# potuino.net
KiCad netlist of a schematic drawn in EAGLE
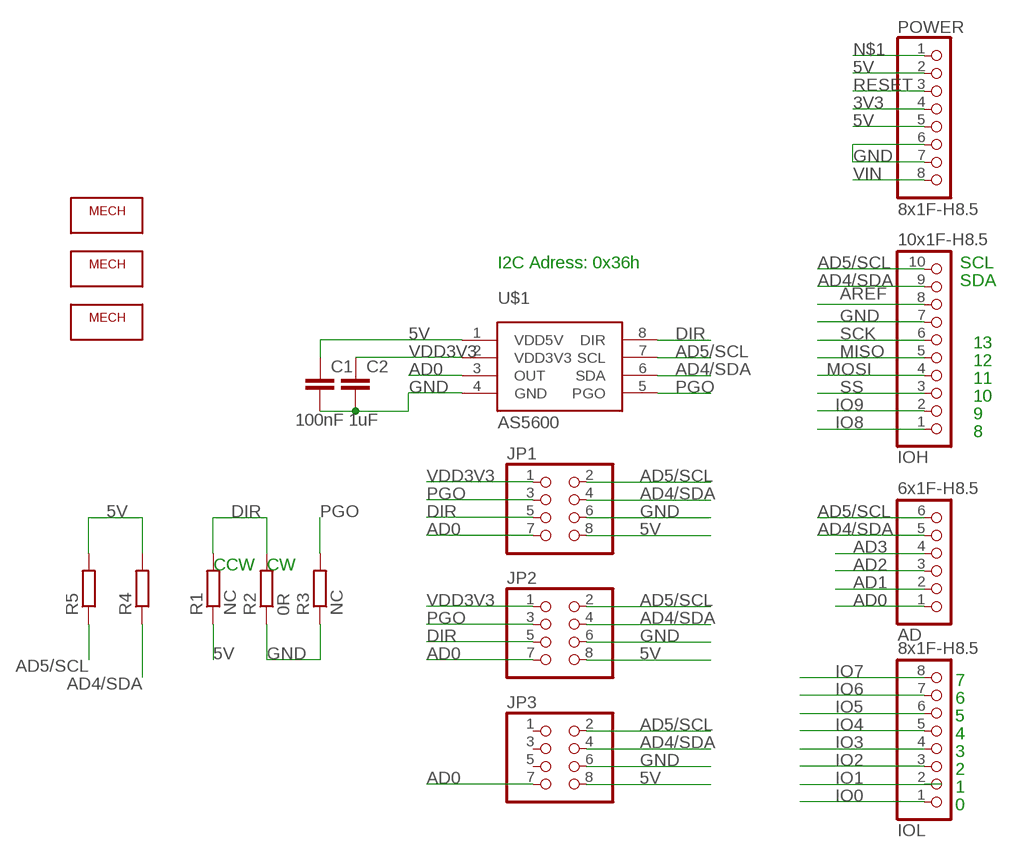
[diagram p0: schematic, sheet 1]

(export (version "E")
  (design (tool "Eeschema 10.0.6"))
  (components
    (comp (ref "AD")
      (value "6x1F-H8.5")
      (footprint "eagle-import:1X06")
      (libsource (lib "eagle-import") (part "PINHD-1X6"))
    )
    (comp (ref "C1")
      (value "100nF")
      (footprint "eagle-import:C0805")
      (libsource (lib "eagle-import") (part "C-EUC0805"))
    )
    (comp (ref "C2")
      (value "1uF")
      (footprint "eagle-import:C0805")
      (libsource (lib "eagle-import") (part "C-EUC0805"))
    )
    (comp (ref "IOH")
      (value "10x1F-H8.5")
      (footprint "eagle-import:1X10")
      (libsource (lib "eagle-import") (part "PINHD-1X10_ARD"))
    )
    (comp (ref "IOL")
      (value "8x1F-H8.5")
      (footprint "eagle-import:1X08")
      (libsource (lib "eagle-import") (part "PINHD-1X8"))
    )
    (comp (ref "JP1")
      (value "PINHD-2X04_2.54")
      (footprint "eagle-import:2X04")
      (libsource (lib "eagle-import") (part "PINHD-2X04_2.54"))
    )
    (comp (ref "JP2")
      (value "PINHD-2X04_2.54")
      (footprint "eagle-import:2X04")
      (libsource (lib "eagle-import") (part "PINHD-2X04_2.54"))
    )
    (comp (ref "JP3")
      (value "PINHD-2X04_2.54")
      (footprint "eagle-import:2X04")
      (libsource (lib "eagle-import") (part "PINHD-2X04_2.54"))
    )
    (comp (ref "POWER")
      (value "8x1F-H8.5")
      (footprint "eagle-import:1X08")
      (libsource (lib "eagle-import") (part "PINHD-1X8"))
    )
    (comp (ref "R1")
      (value "NC")
      (footprint "eagle-import:R0603")
      (libsource (lib "eagle-import") (part "R-EU_R0603"))
    )
    (comp (ref "R2")
      (value "0R")
      (footprint "eagle-import:R0603")
      (libsource (lib "eagle-import") (part "R-EU_R0603"))
    )
    (comp (ref "R3")
      (value "NC")
      (footprint "eagle-import:R0603")
      (libsource (lib "eagle-import") (part "R-EU_R0603"))
    )
    (comp (ref "R4")
      (value "R-EU_R0603")
      (footprint "eagle-import:R0603")
      (libsource (lib "eagle-import") (part "R-EU_R0603"))
    )
    (comp (ref "R5")
      (value "R-EU_R0603")
      (footprint "eagle-import:R0603")
      (libsource (lib "eagle-import") (part "R-EU_R0603"))
    )
    (comp (ref "U$1")
      (value "AS5600")
      (footprint "eagle-import:SO08")
      (libsource (lib "eagle-import") (part "AS5600"))
    )
    (comp (ref "U$2")
      (value "MECHANICAL")
      (footprint "eagle-import:MECHANICAL-PARTS")
      (libsource (lib "eagle-import") (part "MECHANICAL"))
    )
    (comp (ref "U$3")
      (value "MECHANICAL")
      (footprint "eagle-import:MECHANICAL-PARTS")
      (libsource (lib "eagle-import") (part "MECHANICAL"))
    )
    (comp (ref "U$4")
      (value "MECHANICAL2")
      (footprint "eagle-import:MECHANICAL-TOP")
      (libsource (lib "eagle-import") (part "MECHANICAL2"))
    )
  )
  (nets
    (net (code "1") (name "/3V3") (class "Default")
      (node (ref "POWER") (pin "4") (pinfunction "4_4") (pintype "passive"))
    )
    (net (code "2") (name "/5V") (class "Default")
      (node (ref "C1") (pin "1") (pinfunction "1_1") (pintype "passive"))
      (node (ref "JP1") (pin "8") (pinfunction "8_8") (pintype "passive"))
      (node (ref "JP2") (pin "8") (pinfunction "8_8") (pintype "passive"))
      (node (ref "JP3") (pin "8") (pinfunction "8_8") (pintype "passive"))
      (node (ref "POWER") (pin "2") (pinfunction "2_2") (pintype "passive"))
      (node (ref "POWER") (pin "5") (pinfunction "5_5") (pintype "passive"))
      (node (ref "R1") (pin "1") (pinfunction "1_1") (pintype "passive"))
      (node (ref "R4") (pin "2") (pinfunction "2_2") (pintype "passive"))
      (node (ref "R5") (pin "2") (pinfunction "2_2") (pintype "passive"))
      (node (ref "U$1") (pin "1") (pinfunction "VDD5V_1") (pintype "bidirectional"))
    )
    (net (code "3") (name "/AD0") (class "Default")
      (node (ref "AD") (pin "1") (pinfunction "1_1") (pintype "passive"))
      (node (ref "JP1") (pin "7") (pinfunction "7_7") (pintype "passive"))
      (node (ref "JP2") (pin "7") (pinfunction "7_7") (pintype "passive"))
      (node (ref "JP3") (pin "7") (pinfunction "7_7") (pintype "passive"))
      (node (ref "U$1") (pin "3") (pinfunction "OUT_3") (pintype "bidirectional"))
    )
    (net (code "4") (name "/AD1") (class "Default")
      (node (ref "AD") (pin "2") (pinfunction "2_2") (pintype "passive"))
    )
    (net (code "5") (name "/AD2") (class "Default")
      (node (ref "AD") (pin "3") (pinfunction "3_3") (pintype "passive"))
    )
    (net (code "6") (name "/AD3") (class "Default")
      (node (ref "AD") (pin "4") (pinfunction "4_4") (pintype "passive"))
    )
    (net (code "7") (name "/AD4{slash}SDA") (class "Default")
      (node (ref "AD") (pin "5") (pinfunction "5_5") (pintype "passive"))
      (node (ref "IOH") (pin "9") (pinfunction "9_9") (pintype "passive"))
      (node (ref "JP1") (pin "4") (pinfunction "4_4") (pintype "passive"))
      (node (ref "JP2") (pin "4") (pinfunction "4_4") (pintype "passive"))
      (node (ref "JP3") (pin "4") (pinfunction "4_4") (pintype "passive"))
      (node (ref "R4") (pin "1") (pinfunction "1_1") (pintype "passive"))
      (node (ref "U$1") (pin "6") (pinfunction "SDA_6") (pintype "bidirectional"))
    )
    (net (code "8") (name "/AD5{slash}SCL") (class "Default")
      (node (ref "AD") (pin "6") (pinfunction "6_6") (pintype "passive"))
      (node (ref "IOH") (pin "10") (pinfunction "10_10") (pintype "passive"))
      (node (ref "JP1") (pin "2") (pinfunction "2_2") (pintype "passive"))
      (node (ref "JP2") (pin "2") (pinfunction "2_2") (pintype "passive"))
      (node (ref "JP3") (pin "2") (pinfunction "2_2") (pintype "passive"))
      (node (ref "R5") (pin "1") (pinfunction "1_1") (pintype "passive"))
      (node (ref "U$1") (pin "7") (pinfunction "SCL_7") (pintype "bidirectional"))
    )
    (net (code "9") (name "/AREF") (class "Default")
      (node (ref "IOH") (pin "8") (pinfunction "8_8") (pintype "passive"))
    )
    (net (code "10") (name "/DIR") (class "Default")
      (node (ref "JP1") (pin "5") (pinfunction "5_5") (pintype "passive"))
      (node (ref "JP2") (pin "5") (pinfunction "5_5") (pintype "passive"))
      (node (ref "R1") (pin "2") (pinfunction "2_2") (pintype "passive"))
      (node (ref "R2") (pin "2") (pinfunction "2_2") (pintype "passive"))
      (node (ref "U$1") (pin "8") (pinfunction "DIR_8") (pintype "bidirectional"))
    )
    (net (code "11") (name "/GND") (class "Default")
      (node (ref "C1") (pin "2") (pinfunction "2_2") (pintype "passive"))
      (node (ref "C2") (pin "2") (pinfunction "2_2") (pintype "passive"))
      (node (ref "IOH") (pin "7") (pinfunction "7_7") (pintype "passive"))
      (node (ref "JP1") (pin "6") (pinfunction "6_6") (pintype "passive"))
      (node (ref "JP2") (pin "6") (pinfunction "6_6") (pintype "passive"))
      (node (ref "JP3") (pin "6") (pinfunction "6_6") (pintype "passive"))
      (node (ref "POWER") (pin "6") (pinfunction "6_6") (pintype "passive"))
      (node (ref "POWER") (pin "7") (pinfunction "7_7") (pintype "passive"))
      (node (ref "R2") (pin "1") (pinfunction "1_1") (pintype "passive"))
      (node (ref "R3") (pin "1") (pinfunction "1_1") (pintype "passive"))
      (node (ref "U$1") (pin "4") (pinfunction "GND_4") (pintype "bidirectional"))
    )
    (net (code "12") (name "/IO0") (class "Default")
      (node (ref "IOL") (pin "1") (pinfunction "1_1") (pintype "passive"))
    )
    (net (code "13") (name "/IO1") (class "Default")
      (node (ref "IOL") (pin "2") (pinfunction "2_2") (pintype "passive"))
    )
    (net (code "14") (name "/IO2") (class "Default")
      (node (ref "IOL") (pin "3") (pinfunction "3_3") (pintype "passive"))
    )
    (net (code "15") (name "/IO3") (class "Default")
      (node (ref "IOL") (pin "4") (pinfunction "4_4") (pintype "passive"))
    )
    (net (code "16") (name "/IO4") (class "Default")
      (node (ref "IOL") (pin "5") (pinfunction "5_5") (pintype "passive"))
    )
    (net (code "17") (name "/IO5") (class "Default")
      (node (ref "IOL") (pin "6") (pinfunction "6_6") (pintype "passive"))
    )
    (net (code "18") (name "/IO6") (class "Default")
      (node (ref "IOL") (pin "7") (pinfunction "7_7") (pintype "passive"))
    )
    (net (code "19") (name "/IO7") (class "Default")
      (node (ref "IOL") (pin "8") (pinfunction "8_8") (pintype "passive"))
    )
    (net (code "20") (name "/IO8") (class "Default")
      (node (ref "IOH") (pin "1") (pinfunction "1_1") (pintype "passive"))
    )
    (net (code "21") (name "/IO9") (class "Default")
      (node (ref "IOH") (pin "2") (pinfunction "2_2") (pintype "passive"))
    )
    (net (code "22") (name "/MISO") (class "Default")
      (node (ref "IOH") (pin "5") (pinfunction "5_5") (pintype "passive"))
    )
    (net (code "23") (name "/MOSI") (class "Default")
      (node (ref "IOH") (pin "4") (pinfunction "4_4") (pintype "passive"))
    )
    (net (code "24") (name "/N$1") (class "Default")
      (node (ref "POWER") (pin "1") (pinfunction "1_1") (pintype "passive"))
    )
    (net (code "25") (name "/PGO") (class "Default")
      (node (ref "JP1") (pin "3") (pinfunction "3_3") (pintype "passive"))
      (node (ref "JP2") (pin "3") (pinfunction "3_3") (pintype "passive"))
      (node (ref "R3") (pin "2") (pinfunction "2_2") (pintype "passive"))
      (node (ref "U$1") (pin "5") (pinfunction "PGO_5") (pintype "bidirectional"))
    )
    (net (code "26") (name "/RESET") (class "Default")
      (node (ref "POWER") (pin "3") (pinfunction "3_3") (pintype "passive"))
    )
    (net (code "27") (name "/SCK") (class "Default")
      (node (ref "IOH") (pin "6") (pinfunction "6_6") (pintype "passive"))
    )
    (net (code "28") (name "/SS") (class "Default")
      (node (ref "IOH") (pin "3") (pinfunction "3_3") (pintype "passive"))
    )
    (net (code "29") (name "/VDD3V3") (class "Default")
      (node (ref "C2") (pin "1") (pinfunction "1_1") (pintype "passive"))
      (node (ref "JP1") (pin "1") (pinfunction "1_1") (pintype "passive"))
      (node (ref "JP2") (pin "1") (pinfunction "1_1") (pintype "passive"))
      (node (ref "U$1") (pin "2") (pinfunction "VDD3V3_2") (pintype "bidirectional"))
    )
    (net (code "30") (name "/VIN") (class "Default")
      (node (ref "POWER") (pin "8") (pinfunction "8_8") (pintype "passive"))
    )
    (net (code "31") (name "unconnected-(JP3-Pad1)") (class "Default")
      (node (ref "JP3") (pin "1") (pinfunction "1_1") (pintype "passive"))
    )
    (net (code "32") (name "unconnected-(JP3-Pad3)") (class "Default")
      (node (ref "JP3") (pin "3") (pinfunction "3_3") (pintype "passive"))
    )
    (net (code "33") (name "unconnected-(JP3-Pad5)") (class "Default")
      (node (ref "JP3") (pin "5") (pinfunction "5_5") (pintype "passive"))
    )
  )
)
